# NeoDigito_Grande_V2_0.net
KiCad netlist of a schematic drawn in EAGLE
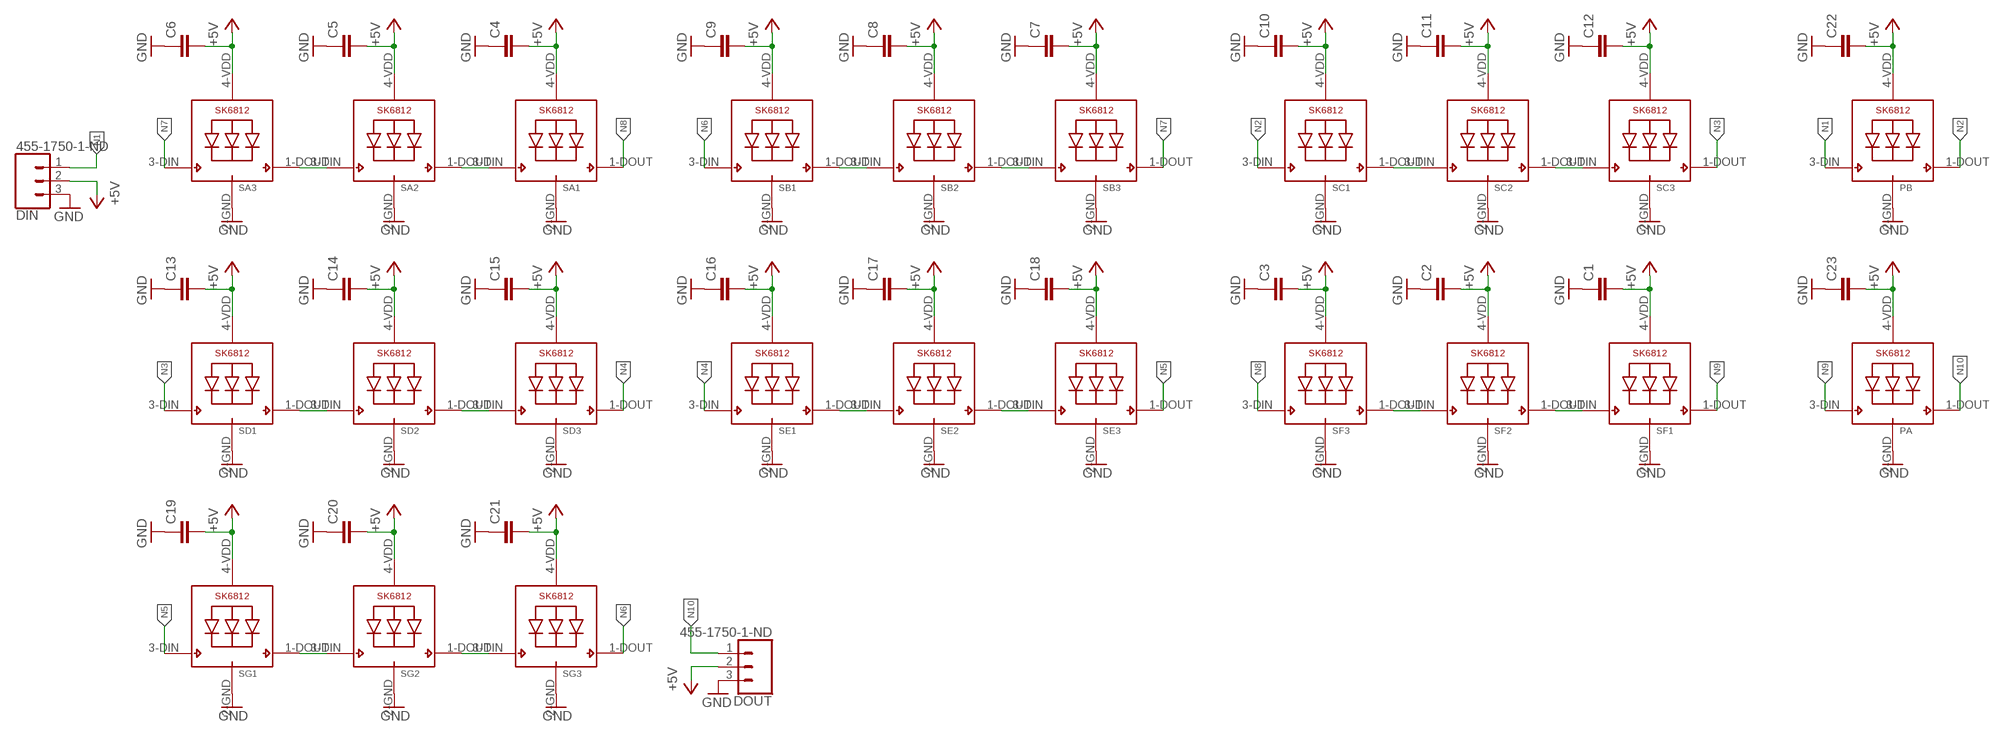
[diagram p0: schematic, sheet 1]

(export (version "E")
  (design (tool "Eeschema 10.0.6"))
  (components
    (comp (ref "C1")
      (value "C-EUC0805")
      (footprint "eagle-import:C0805")
      (libsource (lib "eagle-import") (part "C-EUC0805"))
    )
    (comp (ref "C2")
      (value "C-EUC0805")
      (footprint "eagle-import:C0805")
      (libsource (lib "eagle-import") (part "C-EUC0805"))
    )
    (comp (ref "C3")
      (value "C-EUC0805")
      (footprint "eagle-import:C0805")
      (libsource (lib "eagle-import") (part "C-EUC0805"))
    )
    (comp (ref "C4")
      (value "C-EUC0805")
      (footprint "eagle-import:C0805")
      (libsource (lib "eagle-import") (part "C-EUC0805"))
    )
    (comp (ref "C5")
      (value "C-EUC0805")
      (footprint "eagle-import:C0805")
      (libsource (lib "eagle-import") (part "C-EUC0805"))
    )
    (comp (ref "C6")
      (value "C-EUC0805")
      (footprint "eagle-import:C0805")
      (libsource (lib "eagle-import") (part "C-EUC0805"))
    )
    (comp (ref "C7")
      (value "C-EUC0805")
      (footprint "eagle-import:C0805")
      (libsource (lib "eagle-import") (part "C-EUC0805"))
    )
    (comp (ref "C8")
      (value "C-EUC0805")
      (footprint "eagle-import:C0805")
      (libsource (lib "eagle-import") (part "C-EUC0805"))
    )
    (comp (ref "C9")
      (value "C-EUC0805")
      (footprint "eagle-import:C0805")
      (libsource (lib "eagle-import") (part "C-EUC0805"))
    )
    (comp (ref "C10")
      (value "C-EUC0805")
      (footprint "eagle-import:C0805")
      (libsource (lib "eagle-import") (part "C-EUC0805"))
    )
    (comp (ref "C11")
      (value "C-EUC0805")
      (footprint "eagle-import:C0805")
      (libsource (lib "eagle-import") (part "C-EUC0805"))
    )
    (comp (ref "C12")
      (value "C-EUC0805")
      (footprint "eagle-import:C0805")
      (libsource (lib "eagle-import") (part "C-EUC0805"))
    )
    (comp (ref "C13")
      (value "C-EUC0805")
      (footprint "eagle-import:C0805")
      (libsource (lib "eagle-import") (part "C-EUC0805"))
    )
    (comp (ref "C14")
      (value "C-EUC0805")
      (footprint "eagle-import:C0805")
      (libsource (lib "eagle-import") (part "C-EUC0805"))
    )
    (comp (ref "C15")
      (value "C-EUC0805")
      (footprint "eagle-import:C0805")
      (libsource (lib "eagle-import") (part "C-EUC0805"))
    )
    (comp (ref "C16")
      (value "C-EUC0805")
      (footprint "eagle-import:C0805")
      (libsource (lib "eagle-import") (part "C-EUC0805"))
    )
    (comp (ref "C17")
      (value "C-EUC0805")
      (footprint "eagle-import:C0805")
      (libsource (lib "eagle-import") (part "C-EUC0805"))
    )
    (comp (ref "C18")
      (value "C-EUC0805")
      (footprint "eagle-import:C0805")
      (libsource (lib "eagle-import") (part "C-EUC0805"))
    )
    (comp (ref "C19")
      (value "C-EUC0805")
      (footprint "eagle-import:C0805")
      (libsource (lib "eagle-import") (part "C-EUC0805"))
    )
    (comp (ref "C20")
      (value "C-EUC0805")
      (footprint "eagle-import:C0805")
      (libsource (lib "eagle-import") (part "C-EUC0805"))
    )
    (comp (ref "C21")
      (value "C-EUC0805")
      (footprint "eagle-import:C0805")
      (libsource (lib "eagle-import") (part "C-EUC0805"))
    )
    (comp (ref "C22")
      (value "C-EUC0805")
      (footprint "eagle-import:C0805")
      (libsource (lib "eagle-import") (part "C-EUC0805"))
    )
    (comp (ref "C23")
      (value "C-EUC0805")
      (footprint "eagle-import:C0805")
      (libsource (lib "eagle-import") (part "C-EUC0805"))
    )
    (comp (ref "DIN")
      (value "455-1750-1-ND")
      (footprint "eagle-import:1X03")
      (libsource (lib "eagle-import") (part "CONN_03"))
    )
    (comp (ref "DOUT")
      (value "455-1750-1-ND")
      (footprint "eagle-import:1X03_NO_SILK")
      (libsource (lib "eagle-import") (part "CONN_031X03_NO_SILK"))
    )
    (comp (ref "PA")
      (value "SK6812_3535")
      (footprint "eagle-import:LED3535")
      (libsource (lib "eagle-import") (part "SK6812_3535"))
    )
    (comp (ref "PB")
      (value "SK6812_3535")
      (footprint "eagle-import:LED3535")
      (libsource (lib "eagle-import") (part "SK6812_3535"))
    )
    (comp (ref "SA1")
      (value "SK6812_3535")
      (footprint "eagle-import:LED3535")
      (libsource (lib "eagle-import") (part "SK6812_3535"))
    )
    (comp (ref "SA2")
      (value "SK6812_3535")
      (footprint "eagle-import:LED3535")
      (libsource (lib "eagle-import") (part "SK6812_3535"))
    )
    (comp (ref "SA3")
      (value "SK6812_3535")
      (footprint "eagle-import:LED3535")
      (libsource (lib "eagle-import") (part "SK6812_3535"))
    )
    (comp (ref "SB1")
      (value "SK6812_3535")
      (footprint "eagle-import:LED3535")
      (libsource (lib "eagle-import") (part "SK6812_3535"))
    )
    (comp (ref "SB2")
      (value "SK6812_3535")
      (footprint "eagle-import:LED3535")
      (libsource (lib "eagle-import") (part "SK6812_3535"))
    )
    (comp (ref "SB3")
      (value "SK6812_3535")
      (footprint "eagle-import:LED3535")
      (libsource (lib "eagle-import") (part "SK6812_3535"))
    )
    (comp (ref "SC1")
      (value "SK6812_3535")
      (footprint "eagle-import:LED3535")
      (libsource (lib "eagle-import") (part "SK6812_3535"))
    )
    (comp (ref "SC2")
      (value "SK6812_3535")
      (footprint "eagle-import:LED3535")
      (libsource (lib "eagle-import") (part "SK6812_3535"))
    )
    (comp (ref "SC3")
      (value "SK6812_3535")
      (footprint "eagle-import:LED3535")
      (libsource (lib "eagle-import") (part "SK6812_3535"))
    )
    (comp (ref "SD1")
      (value "SK6812_3535")
      (footprint "eagle-import:LED3535")
      (libsource (lib "eagle-import") (part "SK6812_3535"))
    )
    (comp (ref "SD2")
      (value "SK6812_3535")
      (footprint "eagle-import:LED3535")
      (libsource (lib "eagle-import") (part "SK6812_3535"))
    )
    (comp (ref "SD3")
      (value "SK6812_3535")
      (footprint "eagle-import:LED3535")
      (libsource (lib "eagle-import") (part "SK6812_3535"))
    )
    (comp (ref "SE1")
      (value "SK6812_3535")
      (footprint "eagle-import:LED3535")
      (libsource (lib "eagle-import") (part "SK6812_3535"))
    )
    (comp (ref "SE2")
      (value "SK6812_3535")
      (footprint "eagle-import:LED3535")
      (libsource (lib "eagle-import") (part "SK6812_3535"))
    )
    (comp (ref "SE3")
      (value "SK6812_3535")
      (footprint "eagle-import:LED3535")
      (libsource (lib "eagle-import") (part "SK6812_3535"))
    )
    (comp (ref "SF1")
      (value "SK6812_3535")
      (footprint "eagle-import:LED3535")
      (libsource (lib "eagle-import") (part "SK6812_3535"))
    )
    (comp (ref "SF2")
      (value "SK6812_3535")
      (footprint "eagle-import:LED3535")
      (libsource (lib "eagle-import") (part "SK6812_3535"))
    )
    (comp (ref "SF3")
      (value "SK6812_3535")
      (footprint "eagle-import:LED3535")
      (libsource (lib "eagle-import") (part "SK6812_3535"))
    )
    (comp (ref "SG1")
      (value "SK6812_3535")
      (footprint "eagle-import:LED3535")
      (libsource (lib "eagle-import") (part "SK6812_3535"))
    )
    (comp (ref "SG2")
      (value "SK6812_3535")
      (footprint "eagle-import:LED3535")
      (libsource (lib "eagle-import") (part "SK6812_3535"))
    )
    (comp (ref "SG3")
      (value "SK6812_3535")
      (footprint "eagle-import:LED3535")
      (libsource (lib "eagle-import") (part "SK6812_3535"))
    )
  )
  (nets
    (net (code "1") (name "+5V") (class "Default")
      (node (ref "C1") (pin "2") (pinfunction "2_2") (pintype "passive"))
      (node (ref "C10") (pin "2") (pinfunction "2_2") (pintype "passive"))
      (node (ref "C11") (pin "2") (pinfunction "2_2") (pintype "passive"))
      (node (ref "C12") (pin "2") (pinfunction "2_2") (pintype "passive"))
      (node (ref "C13") (pin "2") (pinfunction "2_2") (pintype "passive"))
      (node (ref "C14") (pin "2") (pinfunction "2_2") (pintype "passive"))
      (node (ref "C15") (pin "2") (pinfunction "2_2") (pintype "passive"))
      (node (ref "C16") (pin "2") (pinfunction "2_2") (pintype "passive"))
      (node (ref "C17") (pin "2") (pinfunction "2_2") (pintype "passive"))
      (node (ref "C18") (pin "2") (pinfunction "2_2") (pintype "passive"))
      (node (ref "C19") (pin "2") (pinfunction "2_2") (pintype "passive"))
      (node (ref "C2") (pin "2") (pinfunction "2_2") (pintype "passive"))
      (node (ref "C20") (pin "2") (pinfunction "2_2") (pintype "passive"))
      (node (ref "C21") (pin "2") (pinfunction "2_2") (pintype "passive"))
      (node (ref "C22") (pin "2") (pinfunction "2_2") (pintype "passive"))
      (node (ref "C23") (pin "2") (pinfunction "2_2") (pintype "passive"))
      (node (ref "C3") (pin "2") (pinfunction "2_2") (pintype "passive"))
      (node (ref "C4") (pin "2") (pinfunction "2_2") (pintype "passive"))
      (node (ref "C5") (pin "2") (pinfunction "2_2") (pintype "passive"))
      (node (ref "C6") (pin "2") (pinfunction "2_2") (pintype "passive"))
      (node (ref "C7") (pin "2") (pinfunction "2_2") (pintype "passive"))
      (node (ref "C8") (pin "2") (pinfunction "2_2") (pintype "passive"))
      (node (ref "C9") (pin "2") (pinfunction "2_2") (pintype "passive"))
      (node (ref "DIN") (pin "2") (pinfunction "2_2") (pintype "passive"))
      (node (ref "DOUT") (pin "2") (pinfunction "2_2") (pintype "passive"))
      (node (ref "PA") (pin "4-VDD") (pinfunction "VDD_4-VDD") (pintype "power_in"))
      (node (ref "PB") (pin "4-VDD") (pinfunction "VDD_4-VDD") (pintype "power_in"))
      (node (ref "SA1") (pin "4-VDD") (pinfunction "VDD_4-VDD") (pintype "power_in"))
      (node (ref "SA2") (pin "4-VDD") (pinfunction "VDD_4-VDD") (pintype "power_in"))
      (node (ref "SA3") (pin "4-VDD") (pinfunction "VDD_4-VDD") (pintype "power_in"))
      (node (ref "SB1") (pin "4-VDD") (pinfunction "VDD_4-VDD") (pintype "power_in"))
      (node (ref "SB2") (pin "4-VDD") (pinfunction "VDD_4-VDD") (pintype "power_in"))
      (node (ref "SB3") (pin "4-VDD") (pinfunction "VDD_4-VDD") (pintype "power_in"))
      (node (ref "SC1") (pin "4-VDD") (pinfunction "VDD_4-VDD") (pintype "power_in"))
      (node (ref "SC2") (pin "4-VDD") (pinfunction "VDD_4-VDD") (pintype "power_in"))
      (node (ref "SC3") (pin "4-VDD") (pinfunction "VDD_4-VDD") (pintype "power_in"))
      (node (ref "SD1") (pin "4-VDD") (pinfunction "VDD_4-VDD") (pintype "power_in"))
      (node (ref "SD2") (pin "4-VDD") (pinfunction "VDD_4-VDD") (pintype "power_in"))
      (node (ref "SD3") (pin "4-VDD") (pinfunction "VDD_4-VDD") (pintype "power_in"))
      (node (ref "SE1") (pin "4-VDD") (pinfunction "VDD_4-VDD") (pintype "power_in"))
      (node (ref "SE2") (pin "4-VDD") (pinfunction "VDD_4-VDD") (pintype "power_in"))
      (node (ref "SE3") (pin "4-VDD") (pinfunction "VDD_4-VDD") (pintype "power_in"))
      (node (ref "SF1") (pin "4-VDD") (pinfunction "VDD_4-VDD") (pintype "power_in"))
      (node (ref "SF2") (pin "4-VDD") (pinfunction "VDD_4-VDD") (pintype "power_in"))
      (node (ref "SF3") (pin "4-VDD") (pinfunction "VDD_4-VDD") (pintype "power_in"))
      (node (ref "SG1") (pin "4-VDD") (pinfunction "VDD_4-VDD") (pintype "power_in"))
      (node (ref "SG2") (pin "4-VDD") (pinfunction "VDD_4-VDD") (pintype "power_in"))
      (node (ref "SG3") (pin "4-VDD") (pinfunction "VDD_4-VDD") (pintype "power_in"))
    )
    (net (code "2") (name "GND") (class "Default")
      (node (ref "C1") (pin "1") (pinfunction "1_1") (pintype "passive"))
      (node (ref "C10") (pin "1") (pinfunction "1_1") (pintype "passive"))
      (node (ref "C11") (pin "1") (pinfunction "1_1") (pintype "passive"))
      (node (ref "C12") (pin "1") (pinfunction "1_1") (pintype "passive"))
      (node (ref "C13") (pin "1") (pinfunction "1_1") (pintype "passive"))
      (node (ref "C14") (pin "1") (pinfunction "1_1") (pintype "passive"))
      (node (ref "C15") (pin "1") (pinfunction "1_1") (pintype "passive"))
      (node (ref "C16") (pin "1") (pinfunction "1_1") (pintype "passive"))
      (node (ref "C17") (pin "1") (pinfunction "1_1") (pintype "passive"))
      (node (ref "C18") (pin "1") (pinfunction "1_1") (pintype "passive"))
      (node (ref "C19") (pin "1") (pinfunction "1_1") (pintype "passive"))
      (node (ref "C2") (pin "1") (pinfunction "1_1") (pintype "passive"))
      (node (ref "C20") (pin "1") (pinfunction "1_1") (pintype "passive"))
      (node (ref "C21") (pin "1") (pinfunction "1_1") (pintype "passive"))
      (node (ref "C22") (pin "1") (pinfunction "1_1") (pintype "passive"))
      (node (ref "C23") (pin "1") (pinfunction "1_1") (pintype "passive"))
      (node (ref "C3") (pin "1") (pinfunction "1_1") (pintype "passive"))
      (node (ref "C4") (pin "1") (pinfunction "1_1") (pintype "passive"))
      (node (ref "C5") (pin "1") (pinfunction "1_1") (pintype "passive"))
      (node (ref "C6") (pin "1") (pinfunction "1_1") (pintype "passive"))
      (node (ref "C7") (pin "1") (pinfunction "1_1") (pintype "passive"))
      (node (ref "C8") (pin "1") (pinfunction "1_1") (pintype "passive"))
      (node (ref "C9") (pin "1") (pinfunction "1_1") (pintype "passive"))
      (node (ref "DIN") (pin "3") (pinfunction "3_3") (pintype "passive"))
      (node (ref "DOUT") (pin "3") (pinfunction "3_3") (pintype "passive"))
      (node (ref "PA") (pin "2-GND") (pinfunction "GND_2-GND") (pintype "power_in"))
      (node (ref "PB") (pin "2-GND") (pinfunction "GND_2-GND") (pintype "power_in"))
      (node (ref "SA1") (pin "2-GND") (pinfunction "GND_2-GND") (pintype "power_in"))
      (node (ref "SA2") (pin "2-GND") (pinfunction "GND_2-GND") (pintype "power_in"))
      (node (ref "SA3") (pin "2-GND") (pinfunction "GND_2-GND") (pintype "power_in"))
      (node (ref "SB1") (pin "2-GND") (pinfunction "GND_2-GND") (pintype "power_in"))
      (node (ref "SB2") (pin "2-GND") (pinfunction "GND_2-GND") (pintype "power_in"))
      (node (ref "SB3") (pin "2-GND") (pinfunction "GND_2-GND") (pintype "power_in"))
      (node (ref "SC1") (pin "2-GND") (pinfunction "GND_2-GND") (pintype "power_in"))
      (node (ref "SC2") (pin "2-GND") (pinfunction "GND_2-GND") (pintype "power_in"))
      (node (ref "SC3") (pin "2-GND") (pinfunction "GND_2-GND") (pintype "power_in"))
      (node (ref "SD1") (pin "2-GND") (pinfunction "GND_2-GND") (pintype "power_in"))
      (node (ref "SD2") (pin "2-GND") (pinfunction "GND_2-GND") (pintype "power_in"))
      (node (ref "SD3") (pin "2-GND") (pinfunction "GND_2-GND") (pintype "power_in"))
      (node (ref "SE1") (pin "2-GND") (pinfunction "GND_2-GND") (pintype "power_in"))
      (node (ref "SE2") (pin "2-GND") (pinfunction "GND_2-GND") (pintype "power_in"))
      (node (ref "SE3") (pin "2-GND") (pinfunction "GND_2-GND") (pintype "power_in"))
      (node (ref "SF1") (pin "2-GND") (pinfunction "GND_2-GND") (pintype "power_in"))
      (node (ref "SF2") (pin "2-GND") (pinfunction "GND_2-GND") (pintype "power_in"))
      (node (ref "SF3") (pin "2-GND") (pinfunction "GND_2-GND") (pintype "power_in"))
      (node (ref "SG1") (pin "2-GND") (pinfunction "GND_2-GND") (pintype "power_in"))
      (node (ref "SG2") (pin "2-GND") (pinfunction "GND_2-GND") (pintype "power_in"))
      (node (ref "SG3") (pin "2-GND") (pinfunction "GND_2-GND") (pintype "power_in"))
    )
    (net (code "3") (name "N1") (class "Default")
      (node (ref "DIN") (pin "1") (pinfunction "1_1") (pintype "passive"))
      (node (ref "PB") (pin "3-DIN") (pinfunction "DI_3-DIN") (pintype "input"))
    )
    (net (code "4") (name "N2") (class "Default")
      (node (ref "PB") (pin "1-DOUT") (pinfunction "DO_1-DOUT") (pintype "output"))
      (node (ref "SC1") (pin "3-DIN") (pinfunction "DI_3-DIN") (pintype "input"))
    )
    (net (code "5") (name "N3") (class "Default")
      (node (ref "SC3") (pin "1-DOUT") (pinfunction "DO_1-DOUT") (pintype "output"))
      (node (ref "SD1") (pin "3-DIN") (pinfunction "DI_3-DIN") (pintype "input"))
    )
    (net (code "6") (name "N4") (class "Default")
      (node (ref "SD3") (pin "1-DOUT") (pinfunction "DO_1-DOUT") (pintype "output"))
      (node (ref "SE1") (pin "3-DIN") (pinfunction "DI_3-DIN") (pintype "input"))
    )
    (net (code "7") (name "N5") (class "Default")
      (node (ref "SE3") (pin "1-DOUT") (pinfunction "DO_1-DOUT") (pintype "output"))
      (node (ref "SG1") (pin "3-DIN") (pinfunction "DI_3-DIN") (pintype "input"))
    )
    (net (code "8") (name "N6") (class "Default")
      (node (ref "SB1") (pin "3-DIN") (pinfunction "DI_3-DIN") (pintype "input"))
      (node (ref "SG3") (pin "1-DOUT") (pinfunction "DO_1-DOUT") (pintype "output"))
    )
    (net (code "9") (name "N7") (class "Default")
      (node (ref "SA3") (pin "3-DIN") (pinfunction "DI_3-DIN") (pintype "input"))
      (node (ref "SB3") (pin "1-DOUT") (pinfunction "DO_1-DOUT") (pintype "output"))
    )
    (net (code "10") (name "N8") (class "Default")
      (node (ref "SA1") (pin "1-DOUT") (pinfunction "DO_1-DOUT") (pintype "output"))
      (node (ref "SF3") (pin "3-DIN") (pinfunction "DI_3-DIN") (pintype "input"))
    )
    (net (code "11") (name "N9") (class "Default")
      (node (ref "PA") (pin "3-DIN") (pinfunction "DI_3-DIN") (pintype "input"))
      (node (ref "SF1") (pin "1-DOUT") (pinfunction "DO_1-DOUT") (pintype "output"))
    )
    (net (code "12") (name "N10") (class "Default")
      (node (ref "DOUT") (pin "1") (pinfunction "1_1") (pintype "passive"))
      (node (ref "PA") (pin "1-DOUT") (pinfunction "DO_1-DOUT") (pintype "output"))
    )
    (net (code "13") (name "Net-(SA1-DI)") (class "Default")
      (node (ref "SA1") (pin "3-DIN") (pinfunction "DI_3-DIN") (pintype "input"))
      (node (ref "SA2") (pin "1-DOUT") (pinfunction "DO_1-DOUT") (pintype "output"))
    )
    (net (code "14") (name "Net-(SA2-DI)") (class "Default")
      (node (ref "SA2") (pin "3-DIN") (pinfunction "DI_3-DIN") (pintype "input"))
      (node (ref "SA3") (pin "1-DOUT") (pinfunction "DO_1-DOUT") (pintype "output"))
    )
    (net (code "15") (name "Net-(SB1-DO)") (class "Default")
      (node (ref "SB1") (pin "1-DOUT") (pinfunction "DO_1-DOUT") (pintype "output"))
      (node (ref "SB2") (pin "3-DIN") (pinfunction "DI_3-DIN") (pintype "input"))
    )
    (net (code "16") (name "Net-(SB2-DO)") (class "Default")
      (node (ref "SB2") (pin "1-DOUT") (pinfunction "DO_1-DOUT") (pintype "output"))
      (node (ref "SB3") (pin "3-DIN") (pinfunction "DI_3-DIN") (pintype "input"))
    )
    (net (code "17") (name "Net-(SC1-DO)") (class "Default")
      (node (ref "SC1") (pin "1-DOUT") (pinfunction "DO_1-DOUT") (pintype "output"))
      (node (ref "SC2") (pin "3-DIN") (pinfunction "DI_3-DIN") (pintype "input"))
    )
    (net (code "18") (name "Net-(SC2-DO)") (class "Default")
      (node (ref "SC2") (pin "1-DOUT") (pinfunction "DO_1-DOUT") (pintype "output"))
      (node (ref "SC3") (pin "3-DIN") (pinfunction "DI_3-DIN") (pintype "input"))
    )
    (net (code "19") (name "Net-(SD1-DO)") (class "Default")
      (node (ref "SD1") (pin "1-DOUT") (pinfunction "DO_1-DOUT") (pintype "output"))
      (node (ref "SD2") (pin "3-DIN") (pinfunction "DI_3-DIN") (pintype "input"))
    )
    (net (code "20") (name "Net-(SD2-DO)") (class "Default")
      (node (ref "SD2") (pin "1-DOUT") (pinfunction "DO_1-DOUT") (pintype "output"))
      (node (ref "SD3") (pin "3-DIN") (pinfunction "DI_3-DIN") (pintype "input"))
    )
    (net (code "21") (name "Net-(SE1-DO)") (class "Default")
      (node (ref "SE1") (pin "1-DOUT") (pinfunction "DO_1-DOUT") (pintype "output"))
      (node (ref "SE2") (pin "3-DIN") (pinfunction "DI_3-DIN") (pintype "input"))
    )
    (net (code "22") (name "Net-(SE2-DO)") (class "Default")
      (node (ref "SE2") (pin "1-DOUT") (pinfunction "DO_1-DOUT") (pintype "output"))
      (node (ref "SE3") (pin "3-DIN") (pinfunction "DI_3-DIN") (pintype "input"))
    )
    (net (code "23") (name "Net-(SF1-DI)") (class "Default")
      (node (ref "SF1") (pin "3-DIN") (pinfunction "DI_3-DIN") (pintype "input"))
      (node (ref "SF2") (pin "1-DOUT") (pinfunction "DO_1-DOUT") (pintype "output"))
    )
    (net (code "24") (name "Net-(SF2-DI)") (class "Default")
      (node (ref "SF2") (pin "3-DIN") (pinfunction "DI_3-DIN") (pintype "input"))
      (node (ref "SF3") (pin "1-DOUT") (pinfunction "DO_1-DOUT") (pintype "output"))
    )
    (net (code "25") (name "Net-(SG1-DO)") (class "Default")
      (node (ref "SG1") (pin "1-DOUT") (pinfunction "DO_1-DOUT") (pintype "output"))
      (node (ref "SG2") (pin "3-DIN") (pinfunction "DI_3-DIN") (pintype "input"))
    )
    (net (code "26") (name "Net-(SG2-DO)") (class "Default")
      (node (ref "SG2") (pin "1-DOUT") (pinfunction "DO_1-DOUT") (pintype "output"))
      (node (ref "SG3") (pin "3-DIN") (pinfunction "DI_3-DIN") (pintype "input"))
    )
  )
)
